# 002_Servos.net
KiCad netlist of a schematic drawn in Altium Designer
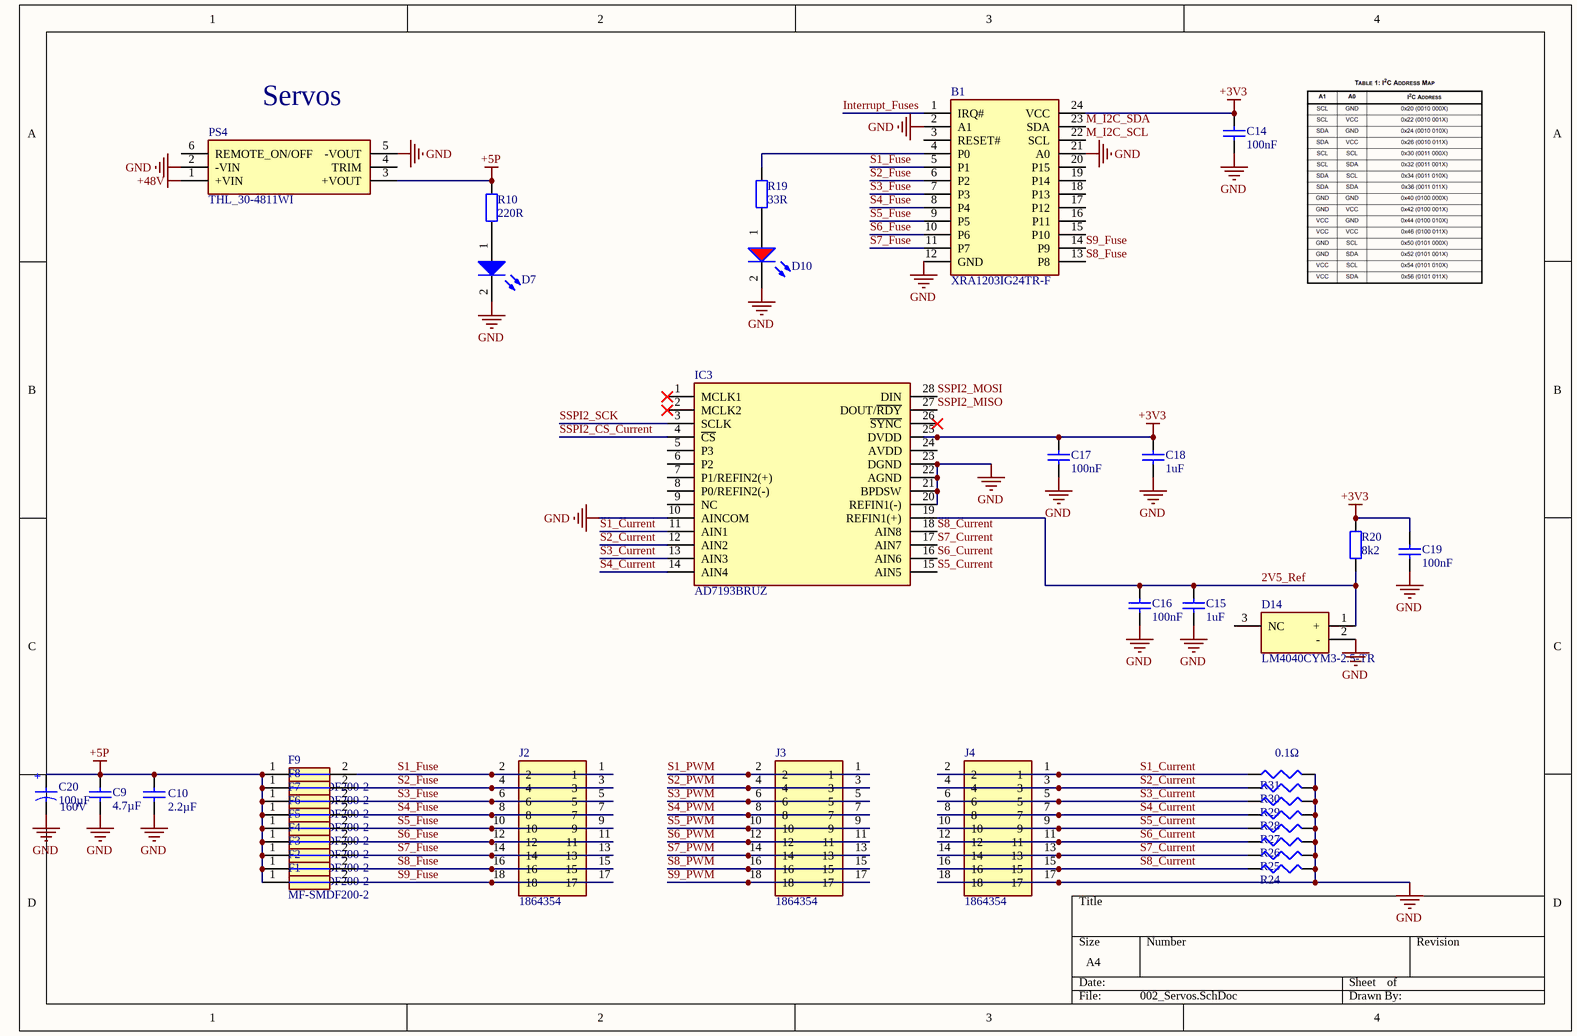
[diagram p0: 002_Servos.SchDoc]

(export (version "E")
  (design (tool "Eeschema 10.0.6"))
  (components
    (comp (ref "B1")
      (value "XRA1203IG24TR-F")
      (footprint "SOP65P640X120-24N")
      (description "Interface - I/O Expanders 16 Bit I2C GPIO Expander")
      (fields (field (name "MOUSER PART NUMBER") "701-XRA1203IG24TR-F"))
      (libsource (lib "XRA1203IG24TR-F") (part "XRA1203IG24TR-F"))
    )
    (comp (ref "C9")
      (value "4.7µF")
      (footprint "WCAP-CSGP_1210_L3.2W2.5H2.5")
      (description "WCAP-CSGP Multilayer Ceramic Chip Capacitor, General Purpose, size 1210, X7R, 4.7µF, 50VDC")
      (fields
        (field (name "MANUFACTURER PART NUMBER") "885012209048")
        (field (name "MANUFACTURER") "Wurth Elektronik")
      )
      (libsource (lib "Altium_WCAP-CSGP (rev22f)") (part "885012209048"))
    )
    (comp (ref "C10")
      (value "2.2µF")
      (footprint "WCAP-CSGP_1812_L4.5W3.2H2.5")
      (description "WCAP-CSGP Multilayer Ceramic Chip Capacitor, General Purpose, size 1812, X7R, 2.2µF, 50VDC")
      (fields
        (field (name "MANUFACTURER PART NUMBER") "885012210032")
        (field (name "MANUFACTURER") "Wurth Elektronik")
      )
      (libsource (lib "Altium_WCAP-CSGP (rev22f)") (part "885012210032"))
    )
    (comp (ref "C14")
      (value "100nF")
      (footprint "Miscellaneous Devices:6-0805_L")
      (description "Capacitor")
      (fields (field (name "PUBLISHER") "Altium Limited"))
      (libsource (lib "Miscellaneous Devices") (part "Cap"))
    )
    (comp (ref "C15")
      (value "1uF")
      (footprint "Miscellaneous Devices:6-0805_L")
      (description "Capacitor")
      (fields (field (name "PUBLISHER") "Altium Limited"))
      (libsource (lib "Miscellaneous Devices") (part "Cap"))
    )
    (comp (ref "C16")
      (value "100nF")
      (footprint "Miscellaneous Devices:6-0805_L")
      (description "Capacitor")
      (fields (field (name "PUBLISHER") "Altium Limited"))
      (libsource (lib "Miscellaneous Devices") (part "Cap"))
    )
    (comp (ref "C17")
      (value "100nF")
      (footprint "Miscellaneous Devices:6-0805_L")
      (description "Capacitor")
      (fields (field (name "PUBLISHER") "Altium Limited"))
      (libsource (lib "Miscellaneous Devices") (part "Cap"))
    )
    (comp (ref "C18")
      (value "1uF")
      (footprint "Miscellaneous Devices:6-0805_L")
      (description "Capacitor")
      (fields (field (name "PUBLISHER") "Altium Limited"))
      (libsource (lib "Miscellaneous Devices") (part "Cap"))
    )
    (comp (ref "C19")
      (value "100nF")
      (footprint "Miscellaneous Devices:6-0805_L")
      (description "Capacitor")
      (fields (field (name "PUBLISHER") "Altium Limited"))
      (libsource (lib "Miscellaneous Devices") (part "Cap"))
    )
    (comp (ref "C20")
      (value "100µF")
      (footprint "WCAP-AT1H_D18H21")
      (description "WCAP-AT1H Aluminum Electrolytic Capacitor, Radial, THT, D18 x H21mm, 100µF, 160V")
      (fields
        (field (name "MANUFACTURER PART NUMBER") "860240981006")
        (field (name "MANUFACTURER") "Wurth Elektronik")
        (field (name "CAPACITANCE") "100µF")
        (field (name "RATED VOLTAGE (DC)") "160V")
      )
      (libsource (lib "Altium_WCAP-AT1H (rev22c)") (part "860240981006"))
    )
    (comp (ref "D7")
      (value "Blue, 3.2V, 140°")
      (footprint "WL-SMCW_0603_150060xx75003")
      (description "WL-SMCW Mono-color Chip LED Waterclear, size 0603, Blue, 3.2V, 140°")
      (fields
        (field (name "MANUFACTURER PART NUMBER") "150060BS75003")
        (field (name "MANUFACTURER") "Wurth Elektronik")
      )
      (libsource (lib "Altium_WL-SMCW (rev22d)") (part "150060BS75003"))
    )
    (comp (ref "D10")
      (value "Red, 2V, 140°")
      (footprint "WL-SMCW_0603_150060xx75003")
      (description "WL-SMCW Mono-color Chip LED Waterclear, size 0603, Red, 2V, 140°")
      (fields
        (field (name "MANUFACTURER PART NUMBER") "150060RS75003")
        (field (name "MANUFACTURER") "Wurth Elektronik")
      )
      (libsource (lib "Altium_WL-SMCW (rev22d)") (part "150060RS75003"))
    )
    (comp (ref "D14")
      (value "LM4040CYM3-2.5-TR")
      (footprint "E-Stall_lib:SOT - 23")
      (description "Integrated Circuit")
      (fields (field (name "MOUSER PART NUMBER") "998-LM4040CYM3-2.5TR"))
      (libsource (lib "SamacSys") (part "LM4040CYM3-2.5-TR"))
    )
    (comp (ref "F1")
      (value "MF-SMDF200-2")
      (footprint "SamacSys:FUSC5146X85N")
      (description "Fuse")
      (fields (field (name "MOUSER PART NUMBER") "652-MF-SMDF200-2"))
      (libsource (lib "*") (part "MF-SMDF200-2"))
    )
    (comp (ref "F2")
      (value "MF-SMDF200-2")
      (footprint "SamacSys:FUSC5146X85N")
      (description "Fuse")
      (fields (field (name "MOUSER PART NUMBER") "652-MF-SMDF200-2"))
      (libsource (lib "*") (part "MF-SMDF200-2"))
    )
    (comp (ref "F3")
      (value "MF-SMDF200-2")
      (footprint "SamacSys:FUSC5146X85N")
      (description "Fuse")
      (fields (field (name "MOUSER PART NUMBER") "652-MF-SMDF200-2"))
      (libsource (lib "*") (part "MF-SMDF200-2"))
    )
    (comp (ref "F4")
      (value "MF-SMDF200-2")
      (footprint "SamacSys:FUSC5146X85N")
      (description "Fuse")
      (fields (field (name "MOUSER PART NUMBER") "652-MF-SMDF200-2"))
      (libsource (lib "*") (part "MF-SMDF200-2"))
    )
    (comp (ref "F5")
      (value "MF-SMDF200-2")
      (footprint "SamacSys:FUSC5146X85N")
      (description "Fuse")
      (fields (field (name "MOUSER PART NUMBER") "652-MF-SMDF200-2"))
      (libsource (lib "*") (part "MF-SMDF200-2"))
    )
    (comp (ref "F6")
      (value "MF-SMDF200-2")
      (footprint "SamacSys:FUSC5146X85N")
      (description "Fuse")
      (fields (field (name "MOUSER PART NUMBER") "652-MF-SMDF200-2"))
      (libsource (lib "*") (part "MF-SMDF200-2"))
    )
    (comp (ref "F7")
      (value "MF-SMDF200-2")
      (footprint "SamacSys:FUSC5146X85N")
      (description "Fuse")
      (fields (field (name "MOUSER PART NUMBER") "652-MF-SMDF200-2"))
      (libsource (lib "*") (part "MF-SMDF200-2"))
    )
    (comp (ref "F8")
      (value "MF-SMDF200-2")
      (footprint "SamacSys:FUSC5146X85N")
      (description "Fuse")
      (fields (field (name "MOUSER PART NUMBER") "652-MF-SMDF200-2"))
      (libsource (lib "*") (part "MF-SMDF200-2"))
    )
    (comp (ref "F9")
      (value "MF-SMDF200-2")
      (footprint "SamacSys:FUSC5146X85N")
      (description "Fuse")
      (fields (field (name "MOUSER PART NUMBER") "652-MF-SMDF200-2"))
      (libsource (lib "*") (part "MF-SMDF200-2"))
    )
    (comp (ref "IC3")
      (value "AD7193BRUZ")
      (footprint "SamacSys:SOP65P640X120-28N")
      (description "Integrated Circuit")
      (fields (field (name "MOUSER PART NUMBER") "584-AD7193BRUZ"))
      (libsource (lib "*") (part "AD7193BRUZ"))
    )
    (comp (ref "J2")
      (value "1864354")
      (footprint "1864354")
      (description "Conn Terminal Block 9 POS 3.5mm Spring Clamp Thru-Hole 13.5A")
      (fields (field (name "MOUSER PART NUMBER") "651-1864354"))
      (libsource (lib "1864354") (part "1864354"))
    )
    (comp (ref "J3")
      (value "1864354")
      (footprint "1864354")
      (description "Conn Terminal Block 9 POS 3.5mm Spring Clamp Thru-Hole 13.5A")
      (fields (field (name "MOUSER PART NUMBER") "651-1864354"))
      (libsource (lib "1864354") (part "1864354"))
    )
    (comp (ref "J4")
      (value "1864354")
      (footprint "1864354")
      (description "Conn Terminal Block 9 POS 3.5mm Spring Clamp Thru-Hole 13.5A")
      (fields (field (name "MOUSER PART NUMBER") "651-1864354"))
      (libsource (lib "1864354") (part "1864354"))
    )
    (comp (ref "PS4")
      (value "THL_30-4811WI")
      (footprint "SamacSys:THL304811WI")
      (description "Power Supply")
      (fields
        (field (name "MANUFACTURER_PART_NUMBER") "THL 30-4811WI")
        (field (name "MOUSER PART NUMBER") "495-THL30-4811WI")
      )
      (libsource (lib "*") (part "THL_30-4811WI"))
    )
    (comp (ref "R10")
      (value "220R")
      (footprint "Miscellaneous Devices:6-0805_M")
      (description "Resistor")
      (fields (field (name "PUBLISHER") "Altium Limited"))
      (libsource (lib "Miscellaneous Devices") (part "Res2"))
    )
    (comp (ref "R19")
      (value "33R")
      (footprint "Miscellaneous Devices:6-0805_M")
      (description "Resistor")
      (fields (field (name "PUBLISHER") "Altium Limited"))
      (libsource (lib "Miscellaneous Devices") (part "Res2"))
    )
    (comp (ref "R20")
      (value "8k2")
      (footprint "Miscellaneous Devices:6-0805_M")
      (description "Resistor")
      (fields (field (name "PUBLISHER") "Altium Limited"))
      (libsource (lib "") (part "Res2_1"))
    )
    (comp (ref "R24")
      (value "0.1Ω")
      (footprint "WRIS-KSKE_0805_L2W1.25H0.6")
      (description "WRIS-KSKE Thick Film Resistor, SMT, size 0805, 0.33W, 0.1Ω, +/-1%")
      (fields
        (field (name "MANUFACTURER PART NUMBER") "560050320001")
        (field (name "MANUFACTURER") "Wurth Elektronik")
      )
      (libsource (lib "Altium_WRIS-KSKE (rev22a)") (part "560050320001"))
    )
    (comp (ref "R25")
      (value "0.1Ω")
      (footprint "WRIS-KSKE_0805_L2W1.25H0.6")
      (description "WRIS-KSKE Thick Film Resistor, SMT, size 0805, 0.33W, 0.1Ω, +/-1%")
      (fields
        (field (name "MANUFACTURER PART NUMBER") "560050320001")
        (field (name "MANUFACTURER") "Wurth Elektronik")
      )
      (libsource (lib "Altium_WRIS-KSKE (rev22a)") (part "560050320001"))
    )
    (comp (ref "R26")
      (value "0.1Ω")
      (footprint "WRIS-KSKE_0805_L2W1.25H0.6")
      (description "WRIS-KSKE Thick Film Resistor, SMT, size 0805, 0.33W, 0.1Ω, +/-1%")
      (fields
        (field (name "MANUFACTURER PART NUMBER") "560050320001")
        (field (name "MANUFACTURER") "Wurth Elektronik")
      )
      (libsource (lib "Altium_WRIS-KSKE (rev22a)") (part "560050320001"))
    )
    (comp (ref "R27")
      (value "0.1Ω")
      (footprint "WRIS-KSKE_0805_L2W1.25H0.6")
      (description "WRIS-KSKE Thick Film Resistor, SMT, size 0805, 0.33W, 0.1Ω, +/-1%")
      (fields
        (field (name "MANUFACTURER PART NUMBER") "560050320001")
        (field (name "MANUFACTURER") "Wurth Elektronik")
      )
      (libsource (lib "Altium_WRIS-KSKE (rev22a)") (part "560050320001"))
    )
    (comp (ref "R28")
      (value "0.1Ω")
      (footprint "WRIS-KSKE_0805_L2W1.25H0.6")
      (description "WRIS-KSKE Thick Film Resistor, SMT, size 0805, 0.33W, 0.1Ω, +/-1%")
      (fields
        (field (name "MANUFACTURER PART NUMBER") "560050320001")
        (field (name "MANUFACTURER") "Wurth Elektronik")
      )
      (libsource (lib "Altium_WRIS-KSKE (rev22a)") (part "560050320001"))
    )
    (comp (ref "R29")
      (value "0.1Ω")
      (footprint "WRIS-KSKE_0805_L2W1.25H0.6")
      (description "WRIS-KSKE Thick Film Resistor, SMT, size 0805, 0.33W, 0.1Ω, +/-1%")
      (fields
        (field (name "MANUFACTURER PART NUMBER") "560050320001")
        (field (name "MANUFACTURER") "Wurth Elektronik")
      )
      (libsource (lib "Altium_WRIS-KSKE (rev22a)") (part "560050320001"))
    )
    (comp (ref "R30")
      (value "0.1Ω")
      (footprint "WRIS-KSKE_0805_L2W1.25H0.6")
      (description "WRIS-KSKE Thick Film Resistor, SMT, size 0805, 0.33W, 0.1Ω, +/-1%")
      (fields
        (field (name "MANUFACTURER PART NUMBER") "560050320001")
        (field (name "MANUFACTURER") "Wurth Elektronik")
      )
      (libsource (lib "Altium_WRIS-KSKE (rev22a)") (part "560050320001"))
    )
    (comp (ref "R31")
      (value "0.1Ω")
      (footprint "WRIS-KSKE_0805_L2W1.25H0.6")
      (description "WRIS-KSKE Thick Film Resistor, SMT, size 0805, 0.33W, 0.1Ω, +/-1%")
      (fields
        (field (name "MANUFACTURER PART NUMBER") "560050320001")
        (field (name "MANUFACTURER") "Wurth Elektronik")
      )
      (libsource (lib "Altium_WRIS-KSKE (rev22a)") (part "560050320001"))
    )
  )
  (nets
    (net (code "1") (name "+3V3") (class "Default")
      (node (ref "B1") (pin "24") (pinfunction "VCC_24") (pintype "passive"))
      (node (ref "C14") (pin "2") (pinfunction "2_2") (pintype "passive"))
      (node (ref "C17") (pin "2") (pinfunction "2_2") (pintype "passive"))
      (node (ref "C18") (pin "2") (pinfunction "2_2") (pintype "passive"))
      (node (ref "C19") (pin "2") (pinfunction "2_2") (pintype "passive"))
      (node (ref "IC3") (pin "25") (pinfunction "DVDD_25") (pintype "passive"))
      (node (ref "R20") (pin "2") (pinfunction "2_2") (pintype "passive"))
    )
    (net (code "2") (name "+5P") (class "Default")
      (node (ref "C10") (pin "2") (pinfunction "2_2") (pintype "passive"))
      (node (ref "C20") (pin "1") (pinfunction "P_1") (pintype "passive"))
      (node (ref "C9") (pin "2") (pinfunction "2_2") (pintype "passive"))
      (node (ref "F1") (pin "1") (pinfunction "1_1") (pintype "passive"))
      (node (ref "F2") (pin "1") (pinfunction "1_1") (pintype "passive"))
      (node (ref "F3") (pin "1") (pinfunction "1_1") (pintype "passive"))
      (node (ref "F4") (pin "1") (pinfunction "1_1") (pintype "passive"))
      (node (ref "F5") (pin "1") (pinfunction "1_1") (pintype "passive"))
      (node (ref "F6") (pin "1") (pinfunction "1_1") (pintype "passive"))
      (node (ref "F7") (pin "1") (pinfunction "1_1") (pintype "passive"))
      (node (ref "F8") (pin "1") (pinfunction "1_1") (pintype "passive"))
      (node (ref "F9") (pin "1") (pinfunction "1_1") (pintype "passive"))
      (node (ref "PS4") (pin "3") (pinfunction "+VOUT_3") (pintype "passive"))
      (node (ref "R10") (pin "2") (pinfunction "2_2") (pintype "passive"))
    )
    (net (code "3") (name "+48V") (class "Default")
      (node (ref "PS4") (pin "1") (pinfunction "+VIN_1") (pintype "passive"))
    )
    (net (code "4") (name "/2V5_Ref") (class "Default")
      (node (ref "C15") (pin "2") (pinfunction "2_2") (pintype "passive"))
      (node (ref "C16") (pin "2") (pinfunction "2_2") (pintype "passive"))
      (node (ref "D14") (pin "1") (pinfunction "+_1") (pintype "passive"))
      (node (ref "IC3") (pin "19") (pinfunction "REFIN1(+)_19") (pintype "passive"))
      (node (ref "R20") (pin "1") (pinfunction "1_1") (pintype "passive"))
    )
    (net (code "5") (name "/Interrupt_Fuses") (class "Default")
      (node (ref "B1") (pin "1") (pinfunction "IRQ#_1") (pintype "passive"))
    )
    (net (code "6") (name "/M_I2C_SCL") (class "Default")
      (node (ref "B1") (pin "22") (pinfunction "SCL_22") (pintype "passive"))
    )
    (net (code "7") (name "/M_I2C_SDA") (class "Default")
      (node (ref "B1") (pin "23") (pinfunction "SDA_23") (pintype "passive"))
    )
    (net (code "8") (name "/S1_Current") (class "Default")
      (node (ref "IC3") (pin "11") (pinfunction "AIN1_11") (pintype "passive"))
      (node (ref "J4") (pin "1") (pinfunction "1_1") (pintype "passive"))
      (node (ref "J4") (pin "2") (pinfunction "2_2") (pintype "passive"))
      (node (ref "R31") (pin "1") (pinfunction "1_1") (pintype "passive"))
    )
    (net (code "9") (name "/S1_Fuse") (class "Default")
      (node (ref "B1") (pin "5") (pinfunction "P1_5") (pintype "passive"))
      (node (ref "F9") (pin "2") (pinfunction "2_2") (pintype "passive"))
      (node (ref "J2") (pin "1") (pinfunction "1_1") (pintype "passive"))
      (node (ref "J2") (pin "2") (pinfunction "2_2") (pintype "passive"))
    )
    (net (code "10") (name "/S1_PWM") (class "Default")
      (node (ref "J3") (pin "1") (pinfunction "1_1") (pintype "passive"))
      (node (ref "J3") (pin "2") (pinfunction "2_2") (pintype "passive"))
    )
    (net (code "11") (name "/S2_Current") (class "Default")
      (node (ref "IC3") (pin "12") (pinfunction "AIN2_12") (pintype "passive"))
      (node (ref "J4") (pin "3") (pinfunction "3_3") (pintype "passive"))
      (node (ref "J4") (pin "4") (pinfunction "4_4") (pintype "passive"))
      (node (ref "R30") (pin "1") (pinfunction "1_1") (pintype "passive"))
    )
    (net (code "12") (name "/S2_Fuse") (class "Default")
      (node (ref "B1") (pin "6") (pinfunction "P2_6") (pintype "passive"))
      (node (ref "F8") (pin "2") (pinfunction "2_2") (pintype "passive"))
      (node (ref "J2") (pin "3") (pinfunction "3_3") (pintype "passive"))
      (node (ref "J2") (pin "4") (pinfunction "4_4") (pintype "passive"))
    )
    (net (code "13") (name "/S2_PWM") (class "Default")
      (node (ref "J3") (pin "3") (pinfunction "3_3") (pintype "passive"))
      (node (ref "J3") (pin "4") (pinfunction "4_4") (pintype "passive"))
    )
    (net (code "14") (name "/S3_Current") (class "Default")
      (node (ref "IC3") (pin "13") (pinfunction "AIN3_13") (pintype "passive"))
      (node (ref "J4") (pin "5") (pinfunction "5_5") (pintype "passive"))
      (node (ref "J4") (pin "6") (pinfunction "6_6") (pintype "passive"))
      (node (ref "R29") (pin "1") (pinfunction "1_1") (pintype "passive"))
    )
    (net (code "15") (name "/S3_Fuse") (class "Default")
      (node (ref "B1") (pin "7") (pinfunction "P3_7") (pintype "passive"))
      (node (ref "F7") (pin "2") (pinfunction "2_2") (pintype "passive"))
      (node (ref "J2") (pin "5") (pinfunction "5_5") (pintype "passive"))
      (node (ref "J2") (pin "6") (pinfunction "6_6") (pintype "passive"))
    )
    (net (code "16") (name "/S3_PWM") (class "Default")
      (node (ref "J3") (pin "5") (pinfunction "5_5") (pintype "passive"))
      (node (ref "J3") (pin "6") (pinfunction "6_6") (pintype "passive"))
    )
    (net (code "17") (name "/S4_Current") (class "Default")
      (node (ref "IC3") (pin "14") (pinfunction "AIN4_14") (pintype "passive"))
      (node (ref "J4") (pin "7") (pinfunction "7_7") (pintype "passive"))
      (node (ref "J4") (pin "8") (pinfunction "8_8") (pintype "passive"))
      (node (ref "R28") (pin "1") (pinfunction "1_1") (pintype "passive"))
    )
    (net (code "18") (name "/S4_Fuse") (class "Default")
      (node (ref "B1") (pin "8") (pinfunction "P4_8") (pintype "passive"))
      (node (ref "F6") (pin "2") (pinfunction "2_2") (pintype "passive"))
      (node (ref "J2") (pin "7") (pinfunction "7_7") (pintype "passive"))
      (node (ref "J2") (pin "8") (pinfunction "8_8") (pintype "passive"))
    )
    (net (code "19") (name "/S4_PWM") (class "Default")
      (node (ref "J3") (pin "7") (pinfunction "7_7") (pintype "passive"))
      (node (ref "J3") (pin "8") (pinfunction "8_8") (pintype "passive"))
    )
    (net (code "20") (name "/S5_Current") (class "Default")
      (node (ref "IC3") (pin "15") (pinfunction "AIN5_15") (pintype "passive"))
      (node (ref "J4") (pin "10") (pinfunction "10_10") (pintype "passive"))
      (node (ref "J4") (pin "9") (pinfunction "9_9") (pintype "passive"))
      (node (ref "R27") (pin "1") (pinfunction "1_1") (pintype "passive"))
    )
    (net (code "21") (name "/S5_Fuse") (class "Default")
      (node (ref "B1") (pin "9") (pinfunction "P5_9") (pintype "passive"))
      (node (ref "F5") (pin "2") (pinfunction "2_2") (pintype "passive"))
      (node (ref "J2") (pin "10") (pinfunction "10_10") (pintype "passive"))
      (node (ref "J2") (pin "9") (pinfunction "9_9") (pintype "passive"))
    )
    (net (code "22") (name "/S5_PWM") (class "Default")
      (node (ref "J3") (pin "10") (pinfunction "10_10") (pintype "passive"))
      (node (ref "J3") (pin "9") (pinfunction "9_9") (pintype "passive"))
    )
    (net (code "23") (name "/S6_Current") (class "Default")
      (node (ref "IC3") (pin "16") (pinfunction "AIN6_16") (pintype "passive"))
      (node (ref "J4") (pin "11") (pinfunction "11_11") (pintype "passive"))
      (node (ref "J4") (pin "12") (pinfunction "12_12") (pintype "passive"))
      (node (ref "R26") (pin "1") (pinfunction "1_1") (pintype "passive"))
    )
    (net (code "24") (name "/S6_Fuse") (class "Default")
      (node (ref "B1") (pin "10") (pinfunction "P6_10") (pintype "passive"))
      (node (ref "F4") (pin "2") (pinfunction "2_2") (pintype "passive"))
      (node (ref "J2") (pin "11") (pinfunction "11_11") (pintype "passive"))
      (node (ref "J2") (pin "12") (pinfunction "12_12") (pintype "passive"))
    )
    (net (code "25") (name "/S6_PWM") (class "Default")
      (node (ref "J3") (pin "11") (pinfunction "11_11") (pintype "passive"))
      (node (ref "J3") (pin "12") (pinfunction "12_12") (pintype "passive"))
    )
    (net (code "26") (name "/S7_Current") (class "Default")
      (node (ref "IC3") (pin "17") (pinfunction "AIN7_17") (pintype "passive"))
      (node (ref "J4") (pin "13") (pinfunction "13_13") (pintype "passive"))
      (node (ref "J4") (pin "14") (pinfunction "14_14") (pintype "passive"))
      (node (ref "R25") (pin "1") (pinfunction "1_1") (pintype "passive"))
    )
    (net (code "27") (name "/S7_Fuse") (class "Default")
      (node (ref "B1") (pin "11") (pinfunction "P7_11") (pintype "passive"))
      (node (ref "F3") (pin "2") (pinfunction "2_2") (pintype "passive"))
      (node (ref "J2") (pin "13") (pinfunction "13_13") (pintype "passive"))
      (node (ref "J2") (pin "14") (pinfunction "14_14") (pintype "passive"))
    )
    (net (code "28") (name "/S7_PWM") (class "Default")
      (node (ref "J3") (pin "13") (pinfunction "13_13") (pintype "passive"))
      (node (ref "J3") (pin "14") (pinfunction "14_14") (pintype "passive"))
    )
    (net (code "29") (name "/S8_Current") (class "Default")
      (node (ref "IC3") (pin "18") (pinfunction "AIN8_18") (pintype "passive"))
      (node (ref "J4") (pin "15") (pinfunction "15_15") (pintype "passive"))
      (node (ref "J4") (pin "16") (pinfunction "16_16") (pintype "passive"))
      (node (ref "R24") (pin "1") (pinfunction "1_1") (pintype "passive"))
    )
    (net (code "30") (name "/S8_Fuse") (class "Default")
      (node (ref "B1") (pin "13") (pinfunction "P8_13") (pintype "passive"))
      (node (ref "F2") (pin "2") (pinfunction "2_2") (pintype "passive"))
      (node (ref "J2") (pin "15") (pinfunction "15_15") (pintype "passive"))
      (node (ref "J2") (pin "16") (pinfunction "16_16") (pintype "passive"))
    )
    (net (code "31") (name "/S8_PWM") (class "Default")
      (node (ref "J3") (pin "15") (pinfunction "15_15") (pintype "passive"))
      (node (ref "J3") (pin "16") (pinfunction "16_16") (pintype "passive"))
    )
    (net (code "32") (name "/S9_Fuse") (class "Default")
      (node (ref "B1") (pin "14") (pinfunction "P9_14") (pintype "passive"))
      (node (ref "F1") (pin "2") (pinfunction "2_2") (pintype "passive"))
      (node (ref "J2") (pin "17") (pinfunction "17_17") (pintype "passive"))
      (node (ref "J2") (pin "18") (pinfunction "18_18") (pintype "passive"))
    )
    (net (code "33") (name "/S9_PWM") (class "Default")
      (node (ref "J3") (pin "17") (pinfunction "17_17") (pintype "passive"))
      (node (ref "J3") (pin "18") (pinfunction "18_18") (pintype "passive"))
    )
    (net (code "34") (name "/SSPI2_CS_Current") (class "Default")
      (node (ref "IC3") (pin "4") (pinfunction "~{CS}_4") (pintype "passive"))
    )
    (net (code "35") (name "/SSPI2_MISO") (class "Default")
      (node (ref "IC3") (pin "27") (pinfunction "DOUT/~{RDY}_27") (pintype "passive"))
    )
    (net (code "36") (name "/SSPI2_MOSI") (class "Default")
      (node (ref "IC3") (pin "28") (pinfunction "DIN_28") (pintype "passive"))
    )
    (net (code "37") (name "/SSPI2_SCK") (class "Default")
      (node (ref "IC3") (pin "3") (pinfunction "SCLK_3") (pintype "passive"))
    )
    (net (code "38") (name "GND") (class "Default")
      (node (ref "B1") (pin "12") (pinfunction "GND_12") (pintype "passive"))
      (node (ref "B1") (pin "2") (pinfunction "A1_2") (pintype "passive"))
      (node (ref "B1") (pin "21") (pinfunction "A0_21") (pintype "passive"))
      (node (ref "C10") (pin "1") (pinfunction "1_1") (pintype "passive"))
      (node (ref "C14") (pin "1") (pinfunction "1_1") (pintype "passive"))
      (node (ref "C15") (pin "1") (pinfunction "1_1") (pintype "passive"))
      (node (ref "C16") (pin "1") (pinfunction "1_1") (pintype "passive"))
      (node (ref "C17") (pin "1") (pinfunction "1_1") (pintype "passive"))
      (node (ref "C18") (pin "1") (pinfunction "1_1") (pintype "passive"))
      (node (ref "C19") (pin "1") (pinfunction "1_1") (pintype "passive"))
      (node (ref "C20") (pin "2") (pinfunction "N_2") (pintype "passive"))
      (node (ref "C9") (pin "1") (pinfunction "1_1") (pintype "passive"))
      (node (ref "D10") (pin "2") (pinfunction "K_2") (pintype "passive"))
      (node (ref "D14") (pin "2") (pinfunction "-_2") (pintype "passive"))
      (node (ref "D7") (pin "2") (pinfunction "K_2") (pintype "passive"))
      (node (ref "IC3") (pin "10") (pinfunction "AINCOM_10") (pintype "passive"))
      (node (ref "IC3") (pin "20") (pinfunction "REFIN1(-)_20") (pintype "passive"))
      (node (ref "IC3") (pin "21") (pinfunction "BPDSW_21") (pintype "passive"))
      (node (ref "IC3") (pin "22") (pinfunction "AGND_22") (pintype "passive"))
      (node (ref "IC3") (pin "23") (pinfunction "DGND_23") (pintype "passive"))
      (node (ref "J4") (pin "17") (pinfunction "17_17") (pintype "passive"))
      (node (ref "J4") (pin "18") (pinfunction "18_18") (pintype "passive"))
      (node (ref "PS4") (pin "2") (pinfunction "-VIN_2") (pintype "passive"))
      (node (ref "PS4") (pin "5") (pinfunction "-VOUT_5") (pintype "passive"))
      (node (ref "R24") (pin "2") (pinfunction "2_2") (pintype "passive"))
      (node (ref "R25") (pin "2") (pinfunction "2_2") (pintype "passive"))
      (node (ref "R26") (pin "2") (pinfunction "2_2") (pintype "passive"))
      (node (ref "R27") (pin "2") (pinfunction "2_2") (pintype "passive"))
      (node (ref "R28") (pin "2") (pinfunction "2_2") (pintype "passive"))
      (node (ref "R29") (pin "2") (pinfunction "2_2") (pintype "passive"))
      (node (ref "R30") (pin "2") (pinfunction "2_2") (pintype "passive"))
      (node (ref "R31") (pin "2") (pinfunction "2_2") (pintype "passive"))
    )
    (net (code "39") (name "Net-(B1-P0)") (class "Default")
      (node (ref "B1") (pin "4") (pinfunction "P0_4") (pintype "passive"))
      (node (ref "R19") (pin "2") (pinfunction "2_2") (pintype "passive"))
    )
    (net (code "40") (name "Net-(D7-A)") (class "Default")
      (node (ref "D7") (pin "1") (pinfunction "A_1") (pintype "passive"))
      (node (ref "R10") (pin "1") (pinfunction "1_1") (pintype "passive"))
    )
    (net (code "41") (name "Net-(D10-A)") (class "Default")
      (node (ref "D10") (pin "1") (pinfunction "A_1") (pintype "passive"))
      (node (ref "R19") (pin "1") (pinfunction "1_1") (pintype "passive"))
    )
    (net (code "42") (name "unconnected-(B1-P10-Pad15)") (class "Default")
      (node (ref "B1") (pin "15") (pinfunction "P10_15") (pintype "passive"))
    )
    (net (code "43") (name "unconnected-(B1-P11-Pad16)") (class "Default")
      (node (ref "B1") (pin "16") (pinfunction "P11_16") (pintype "passive"))
    )
    (net (code "44") (name "unconnected-(B1-P12-Pad17)") (class "Default")
      (node (ref "B1") (pin "17") (pinfunction "P12_17") (pintype "passive"))
    )
    (net (code "45") (name "unconnected-(B1-P13-Pad18)") (class "Default")
      (node (ref "B1") (pin "18") (pinfunction "P13_18") (pintype "passive"))
    )
    (net (code "46") (name "unconnected-(B1-P14-Pad19)") (class "Default")
      (node (ref "B1") (pin "19") (pinfunction "P14_19") (pintype "passive"))
    )
    (net (code "47") (name "unconnected-(B1-P15-Pad20)") (class "Default")
      (node (ref "B1") (pin "20") (pinfunction "P15_20") (pintype "passive"))
    )
    (net (code "48") (name "unconnected-(B1-RESET#-Pad3)") (class "Default")
      (node (ref "B1") (pin "3") (pinfunction "RESET#_3") (pintype "passive"))
    )
    (net (code "49") (name "unconnected-(D14-NC-Pad3)") (class "Default")
      (node (ref "D14") (pin "3") (pinfunction "NC_3") (pintype "passive"))
    )
    (net (code "50") (name "unconnected-(IC3-AVDD-Pad24)") (class "Default")
      (node (ref "IC3") (pin "24") (pinfunction "AVDD_24") (pintype "passive"))
    )
    (net (code "51") (name "unconnected-(IC3-MCLK1-Pad1)") (class "Default")
      (node (ref "IC3") (pin "1") (pinfunction "MCLK1_1") (pintype "passive+no_connect"))
    )
    (net (code "52") (name "unconnected-(IC3-MCLK2-Pad2)") (class "Default")
      (node (ref "IC3") (pin "2") (pinfunction "MCLK2_2") (pintype "passive+no_connect"))
    )
    (net (code "53") (name "unconnected-(IC3-NC-Pad9)") (class "Default")
      (node (ref "IC3") (pin "9") (pinfunction "NC_9") (pintype "passive"))
    )
    (net (code "54") (name "unconnected-(IC3-P0{slash}REFIN2(-)-Pad8)") (class "Default")
      (node (ref "IC3") (pin "8") (pinfunction "P0/REFIN2(-)_8") (pintype "passive"))
    )
    (net (code "55") (name "unconnected-(IC3-P1{slash}REFIN2(+)-Pad7)") (class "Default")
      (node (ref "IC3") (pin "7") (pinfunction "P1/REFIN2(+)_7") (pintype "passive"))
    )
    (net (code "56") (name "unconnected-(IC3-P2-Pad6)") (class "Default")
      (node (ref "IC3") (pin "6") (pinfunction "P2_6") (pintype "passive"))
    )
    (net (code "57") (name "unconnected-(IC3-P3-Pad5)") (class "Default")
      (node (ref "IC3") (pin "5") (pinfunction "P3_5") (pintype "passive"))
    )
    (net (code "58") (name "unconnected-(IC3-~{SYNC}-Pad26)") (class "Default")
      (node (ref "IC3") (pin "26") (pinfunction "~{SYNC}_26") (pintype "passive+no_connect"))
    )
    (net (code "59") (name "unconnected-(PS4-REMOTE_ON{slash}OFF-Pad6)") (class "Default")
      (node (ref "PS4") (pin "6") (pinfunction "REMOTE_ON/OFF_6") (pintype "passive"))
    )
    (net (code "60") (name "unconnected-(PS4-TRIM-Pad4)") (class "Default")
      (node (ref "PS4") (pin "4") (pinfunction "TRIM_4") (pintype "passive"))
    )
  )
)
